# BSPD_4_-_Copy.net
KiCad netlist of a schematic drawn in EAGLE
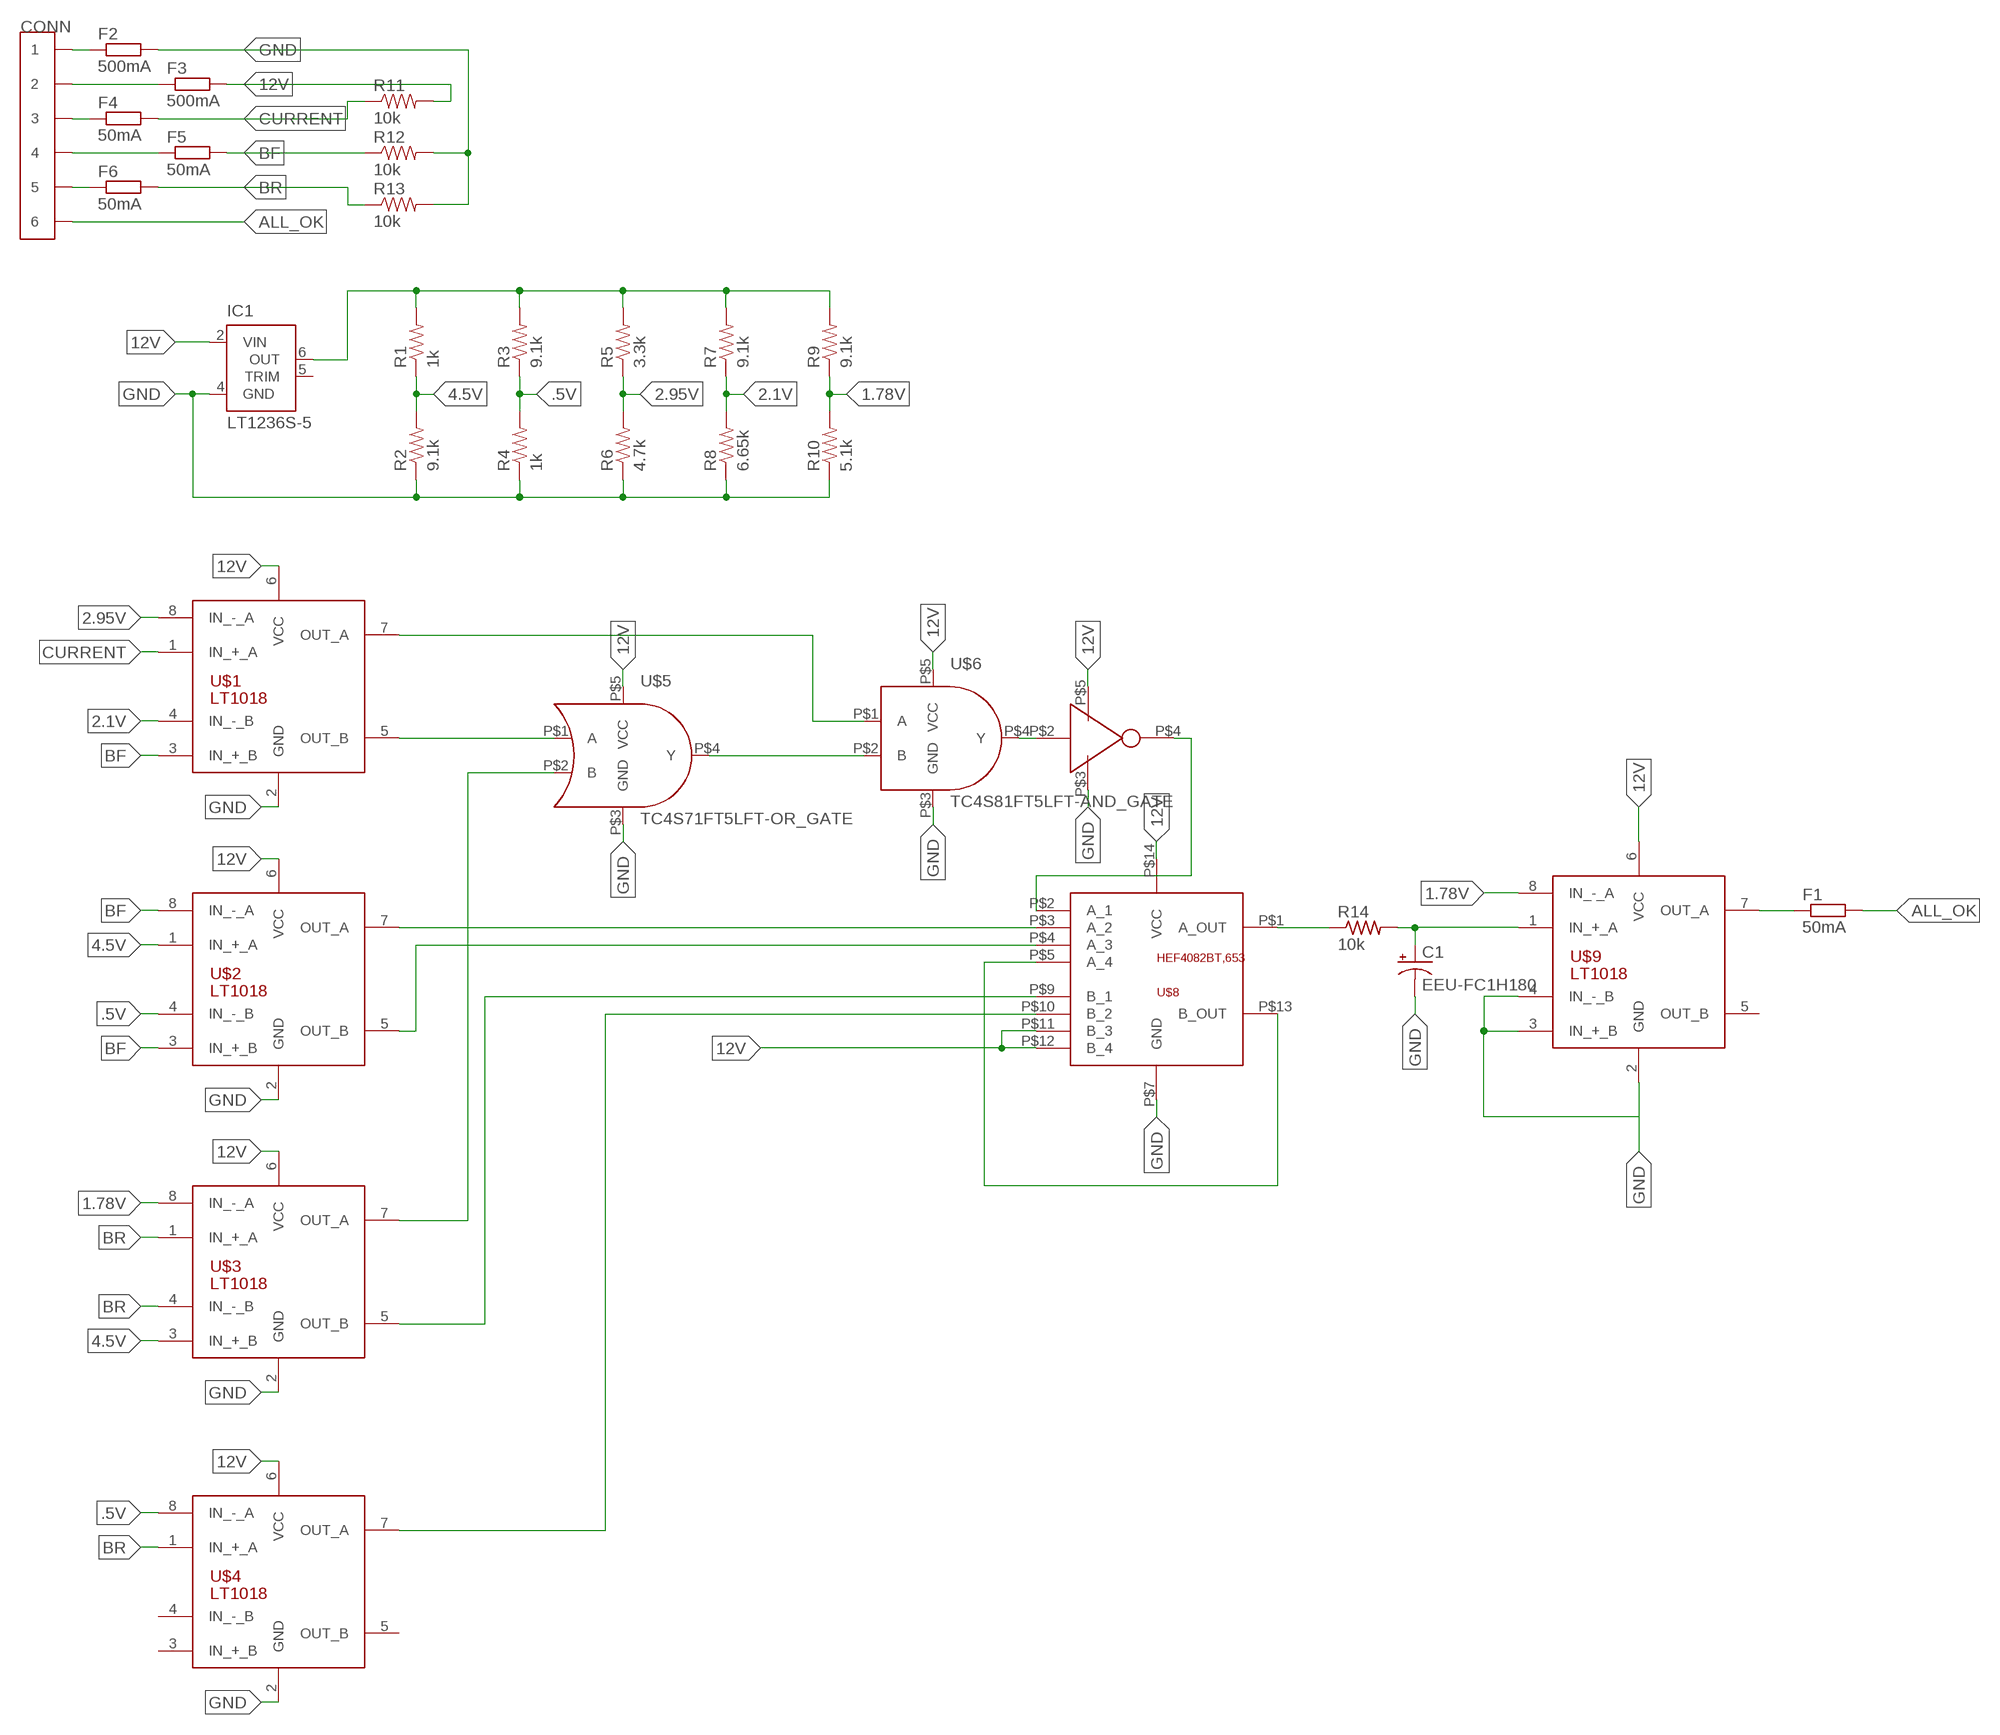
[diagram p0: schematic, sheet 1]

(export (version "E")
  (design (tool "Eeschema 10.0.6"))
  (components
    (comp (ref "C1")
      (value "EEU-FC1H180")
      (footprint "eagle-import:E2-5")
      (libsource (lib "eagle-import") (part "CPOL-USE2-5"))
    )
    (comp (ref "CONN")
      (value "CONN_6")
      (footprint "eagle-import:CONNECTOR_6")
      (libsource (lib "eagle-import") (part "CONN_6"))
    )
    (comp (ref "F1")
      (value "50mA")
      (footprint "eagle-import:R0603")
      (libsource (lib "eagle-import") (part "R-EU_R0603"))
    )
    (comp (ref "F2")
      (value "500mA")
      (footprint "eagle-import:R0603")
      (libsource (lib "eagle-import") (part "R-EU_R0603"))
    )
    (comp (ref "F3")
      (value "500mA")
      (footprint "eagle-import:R0603")
      (libsource (lib "eagle-import") (part "R-EU_R0603"))
    )
    (comp (ref "F4")
      (value "50mA")
      (footprint "eagle-import:R0603")
      (libsource (lib "eagle-import") (part "R-EU_R0603"))
    )
    (comp (ref "F5")
      (value "50mA")
      (footprint "eagle-import:R0603")
      (libsource (lib "eagle-import") (part "R-EU_R0603"))
    )
    (comp (ref "F6")
      (value "50mA")
      (footprint "eagle-import:R0603")
      (libsource (lib "eagle-import") (part "R-EU_R0603"))
    )
    (comp (ref "IC1")
      (value "LT1236S-5")
      (footprint "eagle-import:SOIC8")
      (libsource (lib "eagle-import") (part "LT1236?S-5"))
    )
    (comp (ref "R1")
      (value "1k")
      (footprint "eagle-import:0603-RES")
      (libsource (lib "eagle-import") (part "RESISTOR0603"))
    )
    (comp (ref "R2")
      (value "9.1k")
      (footprint "eagle-import:0603-RES")
      (libsource (lib "eagle-import") (part "RESISTOR0603"))
    )
    (comp (ref "R3")
      (value "9.1k")
      (footprint "eagle-import:0603-RES")
      (libsource (lib "eagle-import") (part "RESISTOR0603"))
    )
    (comp (ref "R4")
      (value "1k")
      (footprint "eagle-import:0603-RES")
      (libsource (lib "eagle-import") (part "RESISTOR0603"))
    )
    (comp (ref "R5")
      (value "3.3k")
      (footprint "eagle-import:0603-RES")
      (libsource (lib "eagle-import") (part "RESISTOR0603"))
    )
    (comp (ref "R6")
      (value "4.7k")
      (footprint "eagle-import:0603-RES")
      (libsource (lib "eagle-import") (part "RESISTOR0603"))
    )
    (comp (ref "R7")
      (value "9.1k")
      (footprint "eagle-import:0603-RES")
      (libsource (lib "eagle-import") (part "RESISTOR0603"))
    )
    (comp (ref "R8")
      (value "6.65k")
      (footprint "eagle-import:0603-RES")
      (libsource (lib "eagle-import") (part "RESISTOR0603"))
    )
    (comp (ref "R9")
      (value "9.1k")
      (footprint "eagle-import:0603-RES")
      (libsource (lib "eagle-import") (part "RESISTOR0603"))
    )
    (comp (ref "R10")
      (value "5.1k")
      (footprint "eagle-import:0603-RES")
      (libsource (lib "eagle-import") (part "RESISTOR0603"))
    )
    (comp (ref "R11")
      (value "10k")
      (footprint "eagle-import:0603-RES")
      (libsource (lib "eagle-import") (part "RESISTOR0603"))
    )
    (comp (ref "R12")
      (value "10k")
      (footprint "eagle-import:0603-RES")
      (libsource (lib "eagle-import") (part "RESISTOR0603"))
    )
    (comp (ref "R13")
      (value "10k")
      (footprint "eagle-import:0603-RES")
      (libsource (lib "eagle-import") (part "RESISTOR0603"))
    )
    (comp (ref "R14")
      (value "10k")
      (footprint "eagle-import:R0603")
      (libsource (lib "eagle-import") (part "R-US_R0603"))
    )
    (comp (ref "U$1")
      (value "LT1018")
      (footprint "eagle-import:SOIC8")
      (libsource (lib "eagle-import") (part "LT1018"))
    )
    (comp (ref "U$2")
      (value "LT1018")
      (footprint "eagle-import:SOIC8")
      (libsource (lib "eagle-import") (part "LT1018"))
    )
    (comp (ref "U$3")
      (value "LT1018")
      (footprint "eagle-import:SOIC8")
      (libsource (lib "eagle-import") (part "LT1018"))
    )
    (comp (ref "U$4")
      (value "LT1018")
      (footprint "eagle-import:SOIC8")
      (libsource (lib "eagle-import") (part "LT1018"))
    )
    (comp (ref "U$5")
      (value "TC4S71FT5LFT-OR_GATE")
      (footprint "eagle-import:SSOP5-P-0.95")
      (libsource (lib "eagle-import") (part "TC4S71FT5LFT-OR_GATE"))
    )
    (comp (ref "U$6")
      (value "TC4S81FT5LFT-AND_GATE")
      (footprint "eagle-import:SSOP5-P-0.95")
      (libsource (lib "eagle-import") (part "TC4S81FT5LFT-AND_GATE"))
    )
    (comp (ref "U$7")
      (value "TC4S69F(TE85L,F)")
      (footprint "eagle-import:SSOP5-P-0.95")
      (libsource (lib "eagle-import") (part "TC4S69F(TE85L,F)"))
    )
    (comp (ref "U$8")
      (value "HEF4082BT,653")
      (footprint "eagle-import:NXP_14_SOIC")
      (libsource (lib "eagle-import") (part "HEF4082BT,653"))
    )
    (comp (ref "U$9")
      (value "LT1018")
      (footprint "eagle-import:SOIC8")
      (libsource (lib "eagle-import") (part "LT1018"))
    )
  )
  (nets
    (net (code "1") (name ".5V") (class "Default")
      (node (ref "R3") (pin "1") (pinfunction "1_1") (pintype "passive"))
      (node (ref "R4") (pin "2") (pinfunction "2_2") (pintype "passive"))
      (node (ref "U$2") (pin "4") (pinfunction "IN_-_B_4") (pintype "input"))
      (node (ref "U$4") (pin "8") (pinfunction "IN_-_A_8") (pintype "input"))
    )
    (net (code "2") (name "1.78V") (class "Default")
      (node (ref "R10") (pin "2") (pinfunction "2_2") (pintype "passive"))
      (node (ref "R9") (pin "1") (pinfunction "1_1") (pintype "passive"))
      (node (ref "U$3") (pin "8") (pinfunction "IN_-_A_8") (pintype "input"))
      (node (ref "U$9") (pin "8") (pinfunction "IN_-_A_8") (pintype "input"))
    )
    (net (code "3") (name "2.1V") (class "Default")
      (node (ref "R7") (pin "1") (pinfunction "1_1") (pintype "passive"))
      (node (ref "R8") (pin "2") (pinfunction "2_2") (pintype "passive"))
      (node (ref "U$1") (pin "4") (pinfunction "IN_-_B_4") (pintype "input"))
    )
    (net (code "4") (name "2.95V") (class "Default")
      (node (ref "R5") (pin "1") (pinfunction "1_1") (pintype "passive"))
      (node (ref "R6") (pin "2") (pinfunction "2_2") (pintype "passive"))
      (node (ref "U$1") (pin "8") (pinfunction "IN_-_A_8") (pintype "input"))
    )
    (net (code "5") (name "4.5V") (class "Default")
      (node (ref "R1") (pin "1") (pinfunction "1_1") (pintype "passive"))
      (node (ref "R2") (pin "2") (pinfunction "2_2") (pintype "passive"))
      (node (ref "U$2") (pin "1") (pinfunction "IN_+_A_1") (pintype "input"))
      (node (ref "U$3") (pin "3") (pinfunction "IN_+_B_3") (pintype "input"))
    )
    (net (code "6") (name "12V") (class "Default")
      (node (ref "F3") (pin "2") (pinfunction "2_2") (pintype "passive"))
      (node (ref "IC1") (pin "2") (pinfunction "VIN_2") (pintype "input"))
      (node (ref "R11") (pin "2") (pinfunction "2_2") (pintype "passive"))
      (node (ref "U$1") (pin "6") (pinfunction "VCC_6") (pintype "power_in"))
      (node (ref "U$2") (pin "6") (pinfunction "VCC_6") (pintype "power_in"))
      (node (ref "U$3") (pin "6") (pinfunction "VCC_6") (pintype "power_in"))
      (node (ref "U$4") (pin "6") (pinfunction "VCC_6") (pintype "power_in"))
      (node (ref "U$5") (pin "P$5") (pinfunction "VCC_P$5") (pintype "bidirectional"))
      (node (ref "U$6") (pin "P$5") (pinfunction "VCC_P$5") (pintype "bidirectional"))
      (node (ref "U$7") (pin "P$5") (pinfunction "VCC_P$5") (pintype "power_in"))
      (node (ref "U$8") (pin "P$11") (pinfunction "B_3_P$11") (pintype "open_collector"))
      (node (ref "U$8") (pin "P$12") (pinfunction "B_4_P$12") (pintype "open_collector"))
      (node (ref "U$8") (pin "P$14") (pinfunction "VCC_P$14") (pintype "power_in"))
      (node (ref "U$9") (pin "6") (pinfunction "VCC_6") (pintype "power_in"))
    )
    (net (code "7") (name "ALL_OK") (class "Default")
      (node (ref "CONN") (pin "11") (pinfunction "6_11") (pintype "bidirectional"))
      (node (ref "CONN") (pin "12") (pinfunction "6_12") (pintype "bidirectional"))
      (node (ref "F1") (pin "2") (pinfunction "2_2") (pintype "passive"))
    )
    (net (code "8") (name "BF") (class "Default")
      (node (ref "F5") (pin "2") (pinfunction "2_2") (pintype "passive"))
      (node (ref "R12") (pin "1") (pinfunction "1_1") (pintype "passive"))
      (node (ref "U$1") (pin "3") (pinfunction "IN_+_B_3") (pintype "input"))
      (node (ref "U$2") (pin "3") (pinfunction "IN_+_B_3") (pintype "input"))
      (node (ref "U$2") (pin "8") (pinfunction "IN_-_A_8") (pintype "input"))
    )
    (net (code "9") (name "BR") (class "Default")
      (node (ref "F6") (pin "2") (pinfunction "2_2") (pintype "passive"))
      (node (ref "R13") (pin "1") (pinfunction "1_1") (pintype "passive"))
      (node (ref "U$3") (pin "1") (pinfunction "IN_+_A_1") (pintype "input"))
      (node (ref "U$3") (pin "4") (pinfunction "IN_-_B_4") (pintype "input"))
      (node (ref "U$4") (pin "1") (pinfunction "IN_+_A_1") (pintype "input"))
    )
    (net (code "10") (name "CURRENT") (class "Default")
      (node (ref "F4") (pin "2") (pinfunction "2_2") (pintype "passive"))
      (node (ref "R11") (pin "1") (pinfunction "1_1") (pintype "passive"))
      (node (ref "U$1") (pin "1") (pinfunction "IN_+_A_1") (pintype "input"))
    )
    (net (code "11") (name "GND") (class "Default")
      (node (ref "C1") (pin "-") (pinfunction "-_-") (pintype "passive"))
      (node (ref "F2") (pin "2") (pinfunction "2_2") (pintype "passive"))
      (node (ref "IC1") (pin "4") (pinfunction "GND_4") (pintype "power_in"))
      (node (ref "R10") (pin "1") (pinfunction "1_1") (pintype "passive"))
      (node (ref "R12") (pin "2") (pinfunction "2_2") (pintype "passive"))
      (node (ref "R13") (pin "2") (pinfunction "2_2") (pintype "passive"))
      (node (ref "R2") (pin "1") (pinfunction "1_1") (pintype "passive"))
      (node (ref "R4") (pin "1") (pinfunction "1_1") (pintype "passive"))
      (node (ref "R6") (pin "1") (pinfunction "1_1") (pintype "passive"))
      (node (ref "R8") (pin "1") (pinfunction "1_1") (pintype "passive"))
      (node (ref "U$1") (pin "2") (pinfunction "GND_2") (pintype "power_in"))
      (node (ref "U$2") (pin "2") (pinfunction "GND_2") (pintype "power_in"))
      (node (ref "U$3") (pin "2") (pinfunction "GND_2") (pintype "power_in"))
      (node (ref "U$4") (pin "2") (pinfunction "GND_2") (pintype "power_in"))
      (node (ref "U$5") (pin "P$3") (pinfunction "GND_P$3") (pintype "bidirectional"))
      (node (ref "U$6") (pin "P$3") (pinfunction "GND_P$3") (pintype "bidirectional"))
      (node (ref "U$7") (pin "P$3") (pinfunction "GND_P$3") (pintype "power_in"))
      (node (ref "U$8") (pin "P$7") (pinfunction "GND_P$7") (pintype "power_in"))
      (node (ref "U$9") (pin "2") (pinfunction "GND_2") (pintype "power_in"))
      (node (ref "U$9") (pin "3") (pinfunction "IN_+_B_3") (pintype "input"))
      (node (ref "U$9") (pin "4") (pinfunction "IN_-_B_4") (pintype "input"))
    )
    (net (code "12") (name "Net-(CONN-1-Pad2)") (class "Default")
      (node (ref "CONN") (pin "1") (pinfunction "1_1") (pintype "bidirectional"))
      (node (ref "CONN") (pin "2") (pinfunction "1_2") (pintype "bidirectional"))
      (node (ref "F2") (pin "1") (pinfunction "1_1") (pintype "passive"))
    )
    (net (code "13") (name "Net-(CONN-2-Pad3)") (class "Default")
      (node (ref "CONN") (pin "3") (pinfunction "2_3") (pintype "bidirectional"))
      (node (ref "CONN") (pin "4") (pinfunction "2_4") (pintype "bidirectional"))
      (node (ref "F3") (pin "1") (pinfunction "1_1") (pintype "passive"))
    )
    (net (code "14") (name "Net-(CONN-3-Pad5)") (class "Default")
      (node (ref "CONN") (pin "5") (pinfunction "3_5") (pintype "bidirectional"))
      (node (ref "CONN") (pin "6") (pinfunction "3_6") (pintype "bidirectional"))
      (node (ref "F4") (pin "1") (pinfunction "1_1") (pintype "passive"))
    )
    (net (code "15") (name "Net-(CONN-4-Pad7)") (class "Default")
      (node (ref "CONN") (pin "7") (pinfunction "4_7") (pintype "bidirectional"))
      (node (ref "CONN") (pin "8") (pinfunction "4_8") (pintype "bidirectional"))
      (node (ref "F5") (pin "1") (pinfunction "1_1") (pintype "passive"))
    )
    (net (code "16") (name "Net-(CONN-5-Pad10)") (class "Default")
      (node (ref "CONN") (pin "10") (pinfunction "5_10") (pintype "bidirectional"))
      (node (ref "CONN") (pin "9") (pinfunction "5_9") (pintype "bidirectional"))
      (node (ref "F6") (pin "1") (pinfunction "1_1") (pintype "passive"))
    )
    (net (code "17") (name "Net-(IC1-OUT)") (class "Default")
      (node (ref "IC1") (pin "6") (pinfunction "OUT_6") (pintype "input"))
      (node (ref "R1") (pin "2") (pinfunction "2_2") (pintype "passive"))
      (node (ref "R3") (pin "2") (pinfunction "2_2") (pintype "passive"))
      (node (ref "R5") (pin "2") (pinfunction "2_2") (pintype "passive"))
      (node (ref "R7") (pin "2") (pinfunction "2_2") (pintype "passive"))
      (node (ref "R9") (pin "2") (pinfunction "2_2") (pintype "passive"))
    )
    (net (code "18") (name "Net-(U$1-OUT_A)") (class "Default")
      (node (ref "U$1") (pin "7") (pinfunction "OUT_A_7") (pintype "output"))
      (node (ref "U$6") (pin "P$1") (pinfunction "A_P$1") (pintype "bidirectional"))
    )
    (net (code "19") (name "Net-(U$1-OUT_B)") (class "Default")
      (node (ref "U$1") (pin "5") (pinfunction "OUT_B_5") (pintype "output"))
      (node (ref "U$5") (pin "P$1") (pinfunction "A_P$1") (pintype "bidirectional"))
    )
    (net (code "20") (name "Net-(U$2-OUT_A)") (class "Default")
      (node (ref "U$2") (pin "7") (pinfunction "OUT_A_7") (pintype "output"))
      (node (ref "U$8") (pin "P$3") (pinfunction "A_2_P$3") (pintype "open_collector"))
    )
    (net (code "21") (name "Net-(U$2-OUT_B)") (class "Default")
      (node (ref "U$2") (pin "5") (pinfunction "OUT_B_5") (pintype "output"))
      (node (ref "U$8") (pin "P$4") (pinfunction "A_3_P$4") (pintype "open_collector"))
    )
    (net (code "22") (name "Net-(U$3-OUT_A)") (class "Default")
      (node (ref "U$3") (pin "7") (pinfunction "OUT_A_7") (pintype "output"))
      (node (ref "U$5") (pin "P$2") (pinfunction "B_P$2") (pintype "bidirectional"))
    )
    (net (code "23") (name "Net-(U$3-OUT_B)") (class "Default")
      (node (ref "U$3") (pin "5") (pinfunction "OUT_B_5") (pintype "output"))
      (node (ref "U$8") (pin "P$9") (pinfunction "B_1_P$9") (pintype "open_collector"))
    )
    (net (code "24") (name "Net-(U$4-OUT_A)") (class "Default")
      (node (ref "U$4") (pin "7") (pinfunction "OUT_A_7") (pintype "output"))
      (node (ref "U$8") (pin "P$10") (pinfunction "B_2_P$10") (pintype "open_collector"))
    )
    (net (code "25") (name "Net-(U$5-Y)") (class "Default")
      (node (ref "U$5") (pin "P$4") (pinfunction "Y_P$4") (pintype "bidirectional"))
      (node (ref "U$6") (pin "P$2") (pinfunction "B_P$2") (pintype "bidirectional"))
    )
    (net (code "26") (name "Net-(U$6-Y)") (class "Default")
      (node (ref "U$6") (pin "P$4") (pinfunction "Y_P$4") (pintype "bidirectional"))
      (node (ref "U$7") (pin "P$2") (pinfunction "IN_P$2") (pintype "input"))
    )
    (net (code "27") (name "Net-(U$7-OUT)") (class "Default")
      (node (ref "U$7") (pin "P$4") (pinfunction "OUT_P$4") (pintype "output"))
      (node (ref "U$8") (pin "P$2") (pinfunction "A_1_P$2") (pintype "open_collector"))
    )
    (net (code "28") (name "Net-(U$8-A_4)") (class "Default")
      (node (ref "U$8") (pin "P$13") (pinfunction "B_OUT_P$13") (pintype "output"))
      (node (ref "U$8") (pin "P$5") (pinfunction "A_4_P$5") (pintype "open_collector"))
    )
    (net (code "29") (name "Net-(U$8-A_OUT)") (class "Default")
      (node (ref "R14") (pin "1") (pinfunction "1_1") (pintype "passive"))
      (node (ref "U$8") (pin "P$1") (pinfunction "A_OUT_P$1") (pintype "output"))
    )
    (net (code "30") (name "Net-(U$9-IN_+_A)") (class "Default")
      (node (ref "C1") (pin "+") (pinfunction "+_+") (pintype "passive"))
      (node (ref "R14") (pin "2") (pinfunction "2_2") (pintype "passive"))
      (node (ref "U$9") (pin "1") (pinfunction "IN_+_A_1") (pintype "input"))
    )
    (net (code "31") (name "Net-(U$9-OUT_A)") (class "Default")
      (node (ref "F1") (pin "1") (pinfunction "1_1") (pintype "passive"))
      (node (ref "U$9") (pin "7") (pinfunction "OUT_A_7") (pintype "output"))
    )
    (net (code "32") (name "unconnected-(IC1-TRIM-Pad5)") (class "Default")
      (node (ref "IC1") (pin "5") (pinfunction "TRIM_5") (pintype "passive"))
    )
    (net (code "33") (name "unconnected-(U$4-IN_+_B-Pad3)") (class "Default")
      (node (ref "U$4") (pin "3") (pinfunction "IN_+_B_3") (pintype "input"))
    )
    (net (code "34") (name "unconnected-(U$4-IN_-_B-Pad4)") (class "Default")
      (node (ref "U$4") (pin "4") (pinfunction "IN_-_B_4") (pintype "input"))
    )
    (net (code "35") (name "unconnected-(U$4-OUT_B-Pad5)") (class "Default")
      (node (ref "U$4") (pin "5") (pinfunction "OUT_B_5") (pintype "output"))
    )
    (net (code "36") (name "unconnected-(U$9-OUT_B-Pad5)") (class "Default")
      (node (ref "U$9") (pin "5") (pinfunction "OUT_B_5") (pintype "output"))
    )
  )
)
